# Ikea_DUKTIG_plates.net
KiCad netlist of a schematic drawn in EAGLE
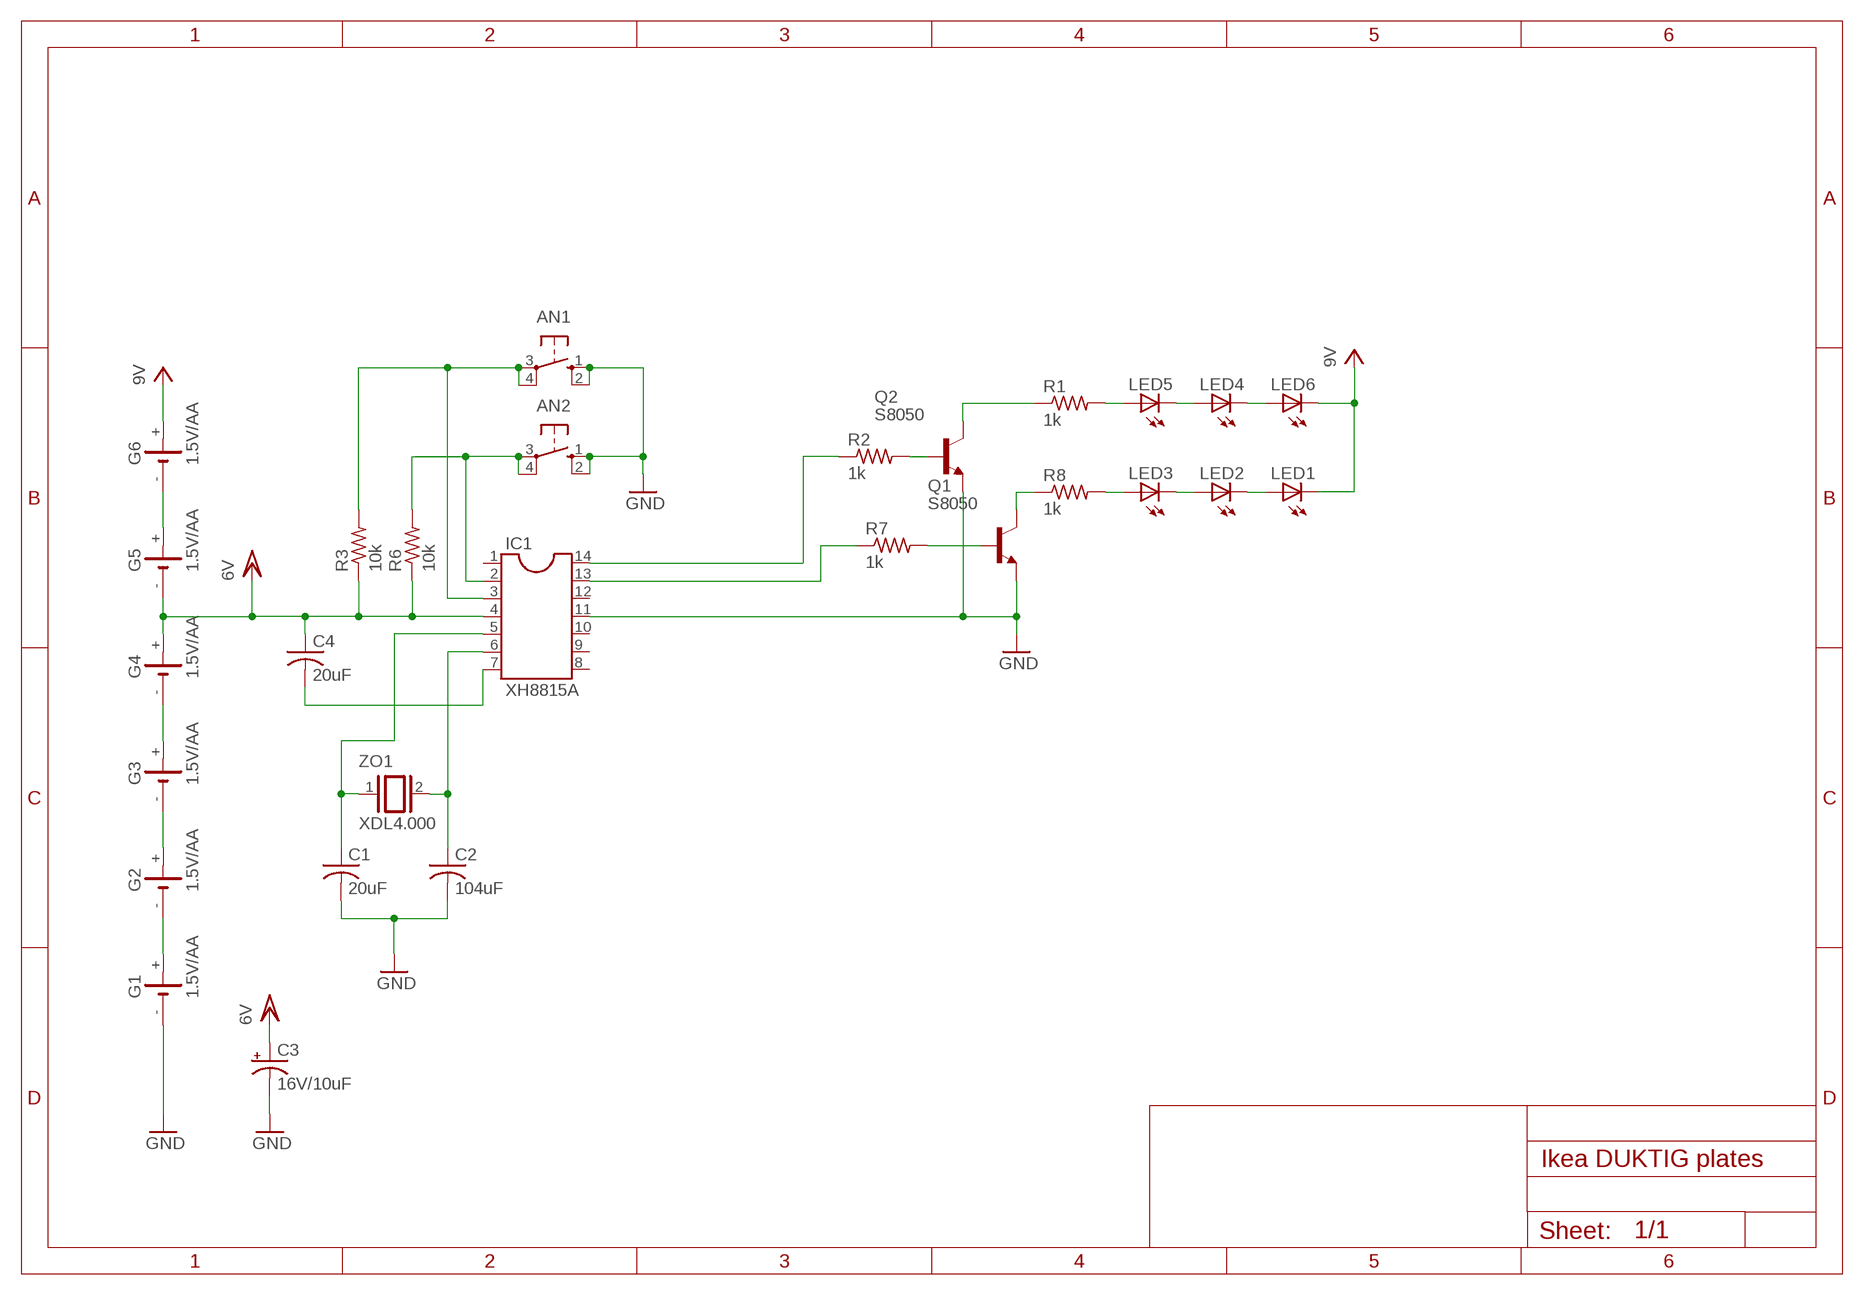
[diagram p0: schematic, sheet 1]

(export (version "E")
  (design (tool "Eeschema 10.0.6"))
  (components
    (comp (ref "AN1")
      (value "40-XX")
      (footprint "eagle-import:B3F-40XX")
      (fields (field (name "MF") "OMRON COMPONENTS USA") (field (name "MPN") "B3F-4000"))
      (libsource (lib "eagle-import") (part "40-XX"))
    )
    (comp (ref "AN2")
      (value "40-XX")
      (footprint "eagle-import:B3F-40XX")
      (fields (field (name "MF") "OMRON COMPONENTS USA") (field (name "MPN") "B3F-4000"))
      (libsource (lib "eagle-import") (part "40-XX"))
    )
    (comp (ref "C1")
      (value "20uF")
      (footprint "eagle-import:C025-024X044")
      (libsource (lib "eagle-import") (part "C-US025-024X044"))
    )
    (comp (ref "C2")
      (value "104uF")
      (footprint "eagle-import:C025-024X044")
      (libsource (lib "eagle-import") (part "C-US025-024X044"))
    )
    (comp (ref "C3")
      (value "16V/10uF")
      (footprint "eagle-import:E2-4")
      (libsource (lib "eagle-import") (part "CPOL-USE2-4"))
    )
    (comp (ref "C4")
      (value "20uF")
      (footprint "eagle-import:C025-024X044")
      (libsource (lib "eagle-import") (part "C-US025-024X044"))
    )
    (comp (ref "G1")
      (value "1.5V/AA")
      (footprint "eagle-import:SL-150-1_2AA_PR")
      (libsource (lib "eagle-import") (part "SL-150-1/2AA/PR"))
    )
    (comp (ref "G2")
      (value "1.5V/AA")
      (footprint "eagle-import:SL-150-1_2AA_PR")
      (libsource (lib "eagle-import") (part "SL-150-1/2AA/PR"))
    )
    (comp (ref "G3")
      (value "1.5V/AA")
      (footprint "eagle-import:SL-150-1_2AA_PR")
      (libsource (lib "eagle-import") (part "SL-150-1/2AA/PR"))
    )
    (comp (ref "G4")
      (value "1.5V/AA")
      (footprint "eagle-import:SL-150-1_2AA_PR")
      (libsource (lib "eagle-import") (part "SL-150-1/2AA/PR"))
    )
    (comp (ref "G5")
      (value "1.5V/AA")
      (footprint "eagle-import:SL-150-1_2AA_PR")
      (libsource (lib "eagle-import") (part "SL-150-1/2AA/PR"))
    )
    (comp (ref "G6")
      (value "1.5V/AA")
      (footprint "eagle-import:SL-150-1_2AA_PR")
      (libsource (lib "eagle-import") (part "SL-150-1/2AA/PR"))
    )
    (comp (ref "IC1")
      (value "XH8815A")
      (footprint "eagle-import:DIL14")
      (libsource (lib "eagle-import") (part "DIL14"))
    )
    (comp (ref "LED1")
      (value "LED5MM")
      (footprint "eagle-import:LED5MM")
      (libsource (lib "eagle-import") (part "LED5MM"))
    )
    (comp (ref "LED2")
      (value "LED5MM")
      (footprint "eagle-import:LED5MM")
      (libsource (lib "eagle-import") (part "LED5MM"))
    )
    (comp (ref "LED3")
      (value "LED5MM")
      (footprint "eagle-import:LED5MM")
      (libsource (lib "eagle-import") (part "LED5MM"))
    )
    (comp (ref "LED4")
      (value "LED5MM")
      (footprint "eagle-import:LED5MM")
      (libsource (lib "eagle-import") (part "LED5MM"))
    )
    (comp (ref "LED5")
      (value "LED5MM")
      (footprint "eagle-import:LED5MM")
      (libsource (lib "eagle-import") (part "LED5MM"))
    )
    (comp (ref "LED6")
      (value "LED5MM")
      (footprint "eagle-import:LED5MM")
      (libsource (lib "eagle-import") (part "LED5MM"))
    )
    (comp (ref "Q1")
      (value "S8050")
      (footprint "eagle-import:TO92-CBE")
      (libsource (lib "eagle-import") (part "-NPN-TO92-CBE"))
    )
    (comp (ref "Q2")
      (value "S8050")
      (footprint "eagle-import:TO92-CBE")
      (libsource (lib "eagle-import") (part "-NPN-TO92-CBE"))
    )
    (comp (ref "R1")
      (value "1k")
      (footprint "eagle-import:0204_5")
      (libsource (lib "eagle-import") (part "R-US_0204/5"))
    )
    (comp (ref "R2")
      (value "1k")
      (footprint "eagle-import:0204_5")
      (libsource (lib "eagle-import") (part "R-US_0204/5"))
    )
    (comp (ref "R3")
      (value "10k")
      (footprint "eagle-import:0204_5")
      (libsource (lib "eagle-import") (part "R-US_0204/5"))
    )
    (comp (ref "R6")
      (value "10k")
      (footprint "eagle-import:0204_5")
      (libsource (lib "eagle-import") (part "R-US_0204/5"))
    )
    (comp (ref "R7")
      (value "1k")
      (footprint "eagle-import:0204_5")
      (libsource (lib "eagle-import") (part "R-US_0204/5"))
    )
    (comp (ref "R8")
      (value "1k")
      (footprint "eagle-import:0204_5")
      (libsource (lib "eagle-import") (part "R-US_0204/5"))
    )
    (comp (ref "ZO1")
      (value "XDL4.000")
      (footprint "eagle-import:QS")
      (libsource (lib "eagle-import") (part "XTAL/S"))
    )
  )
  (nets
    (net (code "1") (name "6V") (class "Default")
      (node (ref "C3") (pin "+") (pinfunction "+_+") (pintype "passive"))
      (node (ref "C4") (pin "1") (pinfunction "1_1") (pintype "passive"))
      (node (ref "G4") (pin "+") (pinfunction "+_+") (pintype "passive"))
      (node (ref "G5") (pin "-") (pinfunction "-_-") (pintype "passive"))
      (node (ref "IC1") (pin "4") (pinfunction "4_4") (pintype "passive"))
      (node (ref "R3") (pin "1") (pinfunction "1_1") (pintype "passive"))
      (node (ref "R6") (pin "1") (pinfunction "1_1") (pintype "passive"))
    )
    (net (code "2") (name "9V") (class "Default")
      (node (ref "G6") (pin "+") (pinfunction "+_+") (pintype "passive"))
      (node (ref "LED1") (pin "K") (pinfunction "C_K") (pintype "passive"))
      (node (ref "LED6") (pin "K") (pinfunction "C_K") (pintype "passive"))
    )
    (net (code "3") (name "GND") (class "Default")
      (node (ref "AN1") (pin "1") (pinfunction "S_1") (pintype "passive"))
      (node (ref "AN1") (pin "2") (pinfunction "S1_2") (pintype "passive"))
      (node (ref "AN2") (pin "1") (pinfunction "S_1") (pintype "passive"))
      (node (ref "AN2") (pin "2") (pinfunction "S1_2") (pintype "passive"))
      (node (ref "C1") (pin "2") (pinfunction "2_2") (pintype "passive"))
      (node (ref "C2") (pin "2") (pinfunction "2_2") (pintype "passive"))
      (node (ref "C3") (pin "-") (pinfunction "-_-") (pintype "passive"))
      (node (ref "G1") (pin "-") (pinfunction "-_-") (pintype "passive"))
      (node (ref "IC1") (pin "11") (pinfunction "11_11") (pintype "passive"))
      (node (ref "Q1") (pin "E") (pinfunction "E_E") (pintype "passive"))
      (node (ref "Q2") (pin "E") (pinfunction "E_E") (pintype "passive"))
    )
    (net (code "4") (name "Net-(AN1-P)") (class "Default")
      (node (ref "AN1") (pin "3") (pinfunction "P_3") (pintype "passive"))
      (node (ref "AN1") (pin "4") (pinfunction "P1_4") (pintype "passive"))
      (node (ref "IC1") (pin "3") (pinfunction "3_3") (pintype "passive"))
      (node (ref "R3") (pin "2") (pinfunction "2_2") (pintype "passive"))
    )
    (net (code "5") (name "Net-(AN2-P)") (class "Default")
      (node (ref "AN2") (pin "3") (pinfunction "P_3") (pintype "passive"))
      (node (ref "AN2") (pin "4") (pinfunction "P1_4") (pintype "passive"))
      (node (ref "IC1") (pin "2") (pinfunction "2_2") (pintype "passive"))
      (node (ref "R6") (pin "2") (pinfunction "2_2") (pintype "passive"))
    )
    (net (code "6") (name "Net-(C1-Pad1)") (class "Default")
      (node (ref "C1") (pin "1") (pinfunction "1_1") (pintype "passive"))
      (node (ref "IC1") (pin "5") (pinfunction "5_5") (pintype "passive"))
      (node (ref "ZO1") (pin "1") (pinfunction "1_1") (pintype "passive"))
    )
    (net (code "7") (name "Net-(C2-Pad1)") (class "Default")
      (node (ref "C2") (pin "1") (pinfunction "1_1") (pintype "passive"))
      (node (ref "IC1") (pin "6") (pinfunction "6_6") (pintype "passive"))
      (node (ref "ZO1") (pin "2") (pinfunction "2_2") (pintype "passive"))
    )
    (net (code "8") (name "Net-(C4-Pad2)") (class "Default")
      (node (ref "C4") (pin "2") (pinfunction "2_2") (pintype "passive"))
      (node (ref "IC1") (pin "7") (pinfunction "7_7") (pintype "passive"))
    )
    (net (code "9") (name "Net-(G1-Pad+)") (class "Default")
      (node (ref "G1") (pin "+") (pinfunction "+_+") (pintype "passive"))
      (node (ref "G2") (pin "-") (pinfunction "-_-") (pintype "passive"))
    )
    (net (code "10") (name "Net-(G2-Pad+)") (class "Default")
      (node (ref "G2") (pin "+") (pinfunction "+_+") (pintype "passive"))
      (node (ref "G3") (pin "-") (pinfunction "-_-") (pintype "passive"))
    )
    (net (code "11") (name "Net-(G3-Pad+)") (class "Default")
      (node (ref "G3") (pin "+") (pinfunction "+_+") (pintype "passive"))
      (node (ref "G4") (pin "-") (pinfunction "-_-") (pintype "passive"))
    )
    (net (code "12") (name "Net-(G5-Pad+)") (class "Default")
      (node (ref "G5") (pin "+") (pinfunction "+_+") (pintype "passive"))
      (node (ref "G6") (pin "-") (pinfunction "-_-") (pintype "passive"))
    )
    (net (code "13") (name "Net-(IC1-Pad13)") (class "Default")
      (node (ref "IC1") (pin "13") (pinfunction "13_13") (pintype "passive"))
      (node (ref "R7") (pin "1") (pinfunction "1_1") (pintype "passive"))
    )
    (net (code "14") (name "Net-(IC1-Pad14)") (class "Default")
      (node (ref "IC1") (pin "14") (pinfunction "14_14") (pintype "passive"))
      (node (ref "R2") (pin "1") (pinfunction "1_1") (pintype "passive"))
    )
    (net (code "15") (name "Net-(LED2-C)") (class "Default")
      (node (ref "LED1") (pin "A") (pinfunction "A_A") (pintype "passive"))
      (node (ref "LED2") (pin "K") (pinfunction "C_K") (pintype "passive"))
    )
    (net (code "16") (name "Net-(LED3-C)") (class "Default")
      (node (ref "LED2") (pin "A") (pinfunction "A_A") (pintype "passive"))
      (node (ref "LED3") (pin "K") (pinfunction "C_K") (pintype "passive"))
    )
    (net (code "17") (name "Net-(LED3-PadA)") (class "Default")
      (node (ref "LED3") (pin "A") (pinfunction "A_A") (pintype "passive"))
      (node (ref "R8") (pin "2") (pinfunction "2_2") (pintype "passive"))
    )
    (net (code "18") (name "Net-(LED4-C)") (class "Default")
      (node (ref "LED4") (pin "K") (pinfunction "C_K") (pintype "passive"))
      (node (ref "LED6") (pin "A") (pinfunction "A_A") (pintype "passive"))
    )
    (net (code "19") (name "Net-(LED5-C)") (class "Default")
      (node (ref "LED4") (pin "A") (pinfunction "A_A") (pintype "passive"))
      (node (ref "LED5") (pin "K") (pinfunction "C_K") (pintype "passive"))
    )
    (net (code "20") (name "Net-(LED5-PadA)") (class "Default")
      (node (ref "LED5") (pin "A") (pinfunction "A_A") (pintype "passive"))
      (node (ref "R1") (pin "2") (pinfunction "2_2") (pintype "passive"))
    )
    (net (code "21") (name "Net-(Q1-PadB)") (class "Default")
      (node (ref "Q1") (pin "B") (pinfunction "B_B") (pintype "passive"))
      (node (ref "R7") (pin "2") (pinfunction "2_2") (pintype "passive"))
    )
    (net (code "22") (name "Net-(Q1-PadC)") (class "Default")
      (node (ref "Q1") (pin "C") (pinfunction "C_C") (pintype "passive"))
      (node (ref "R8") (pin "1") (pinfunction "1_1") (pintype "passive"))
    )
    (net (code "23") (name "Net-(Q2-PadB)") (class "Default")
      (node (ref "Q2") (pin "B") (pinfunction "B_B") (pintype "passive"))
      (node (ref "R2") (pin "2") (pinfunction "2_2") (pintype "passive"))
    )
    (net (code "24") (name "Net-(Q2-PadC)") (class "Default")
      (node (ref "Q2") (pin "C") (pinfunction "C_C") (pintype "passive"))
      (node (ref "R1") (pin "1") (pinfunction "1_1") (pintype "passive"))
    )
    (net (code "25") (name "unconnected-(IC1-Pad1)") (class "Default")
      (node (ref "IC1") (pin "1") (pinfunction "1_1") (pintype "passive"))
    )
    (net (code "26") (name "unconnected-(IC1-Pad8)") (class "Default")
      (node (ref "IC1") (pin "8") (pinfunction "8_8") (pintype "passive"))
    )
    (net (code "27") (name "unconnected-(IC1-Pad9)") (class "Default")
      (node (ref "IC1") (pin "9") (pinfunction "9_9") (pintype "passive"))
    )
    (net (code "28") (name "unconnected-(IC1-Pad10)") (class "Default")
      (node (ref "IC1") (pin "10") (pinfunction "10_10") (pintype "passive"))
    )
    (net (code "29") (name "unconnected-(IC1-Pad12)") (class "Default")
      (node (ref "IC1") (pin "12") (pinfunction "12_12") (pintype "passive"))
    )
  )
)
